# Pwr_Brd_4.net
KiCad netlist of a schematic drawn in Altium Designer
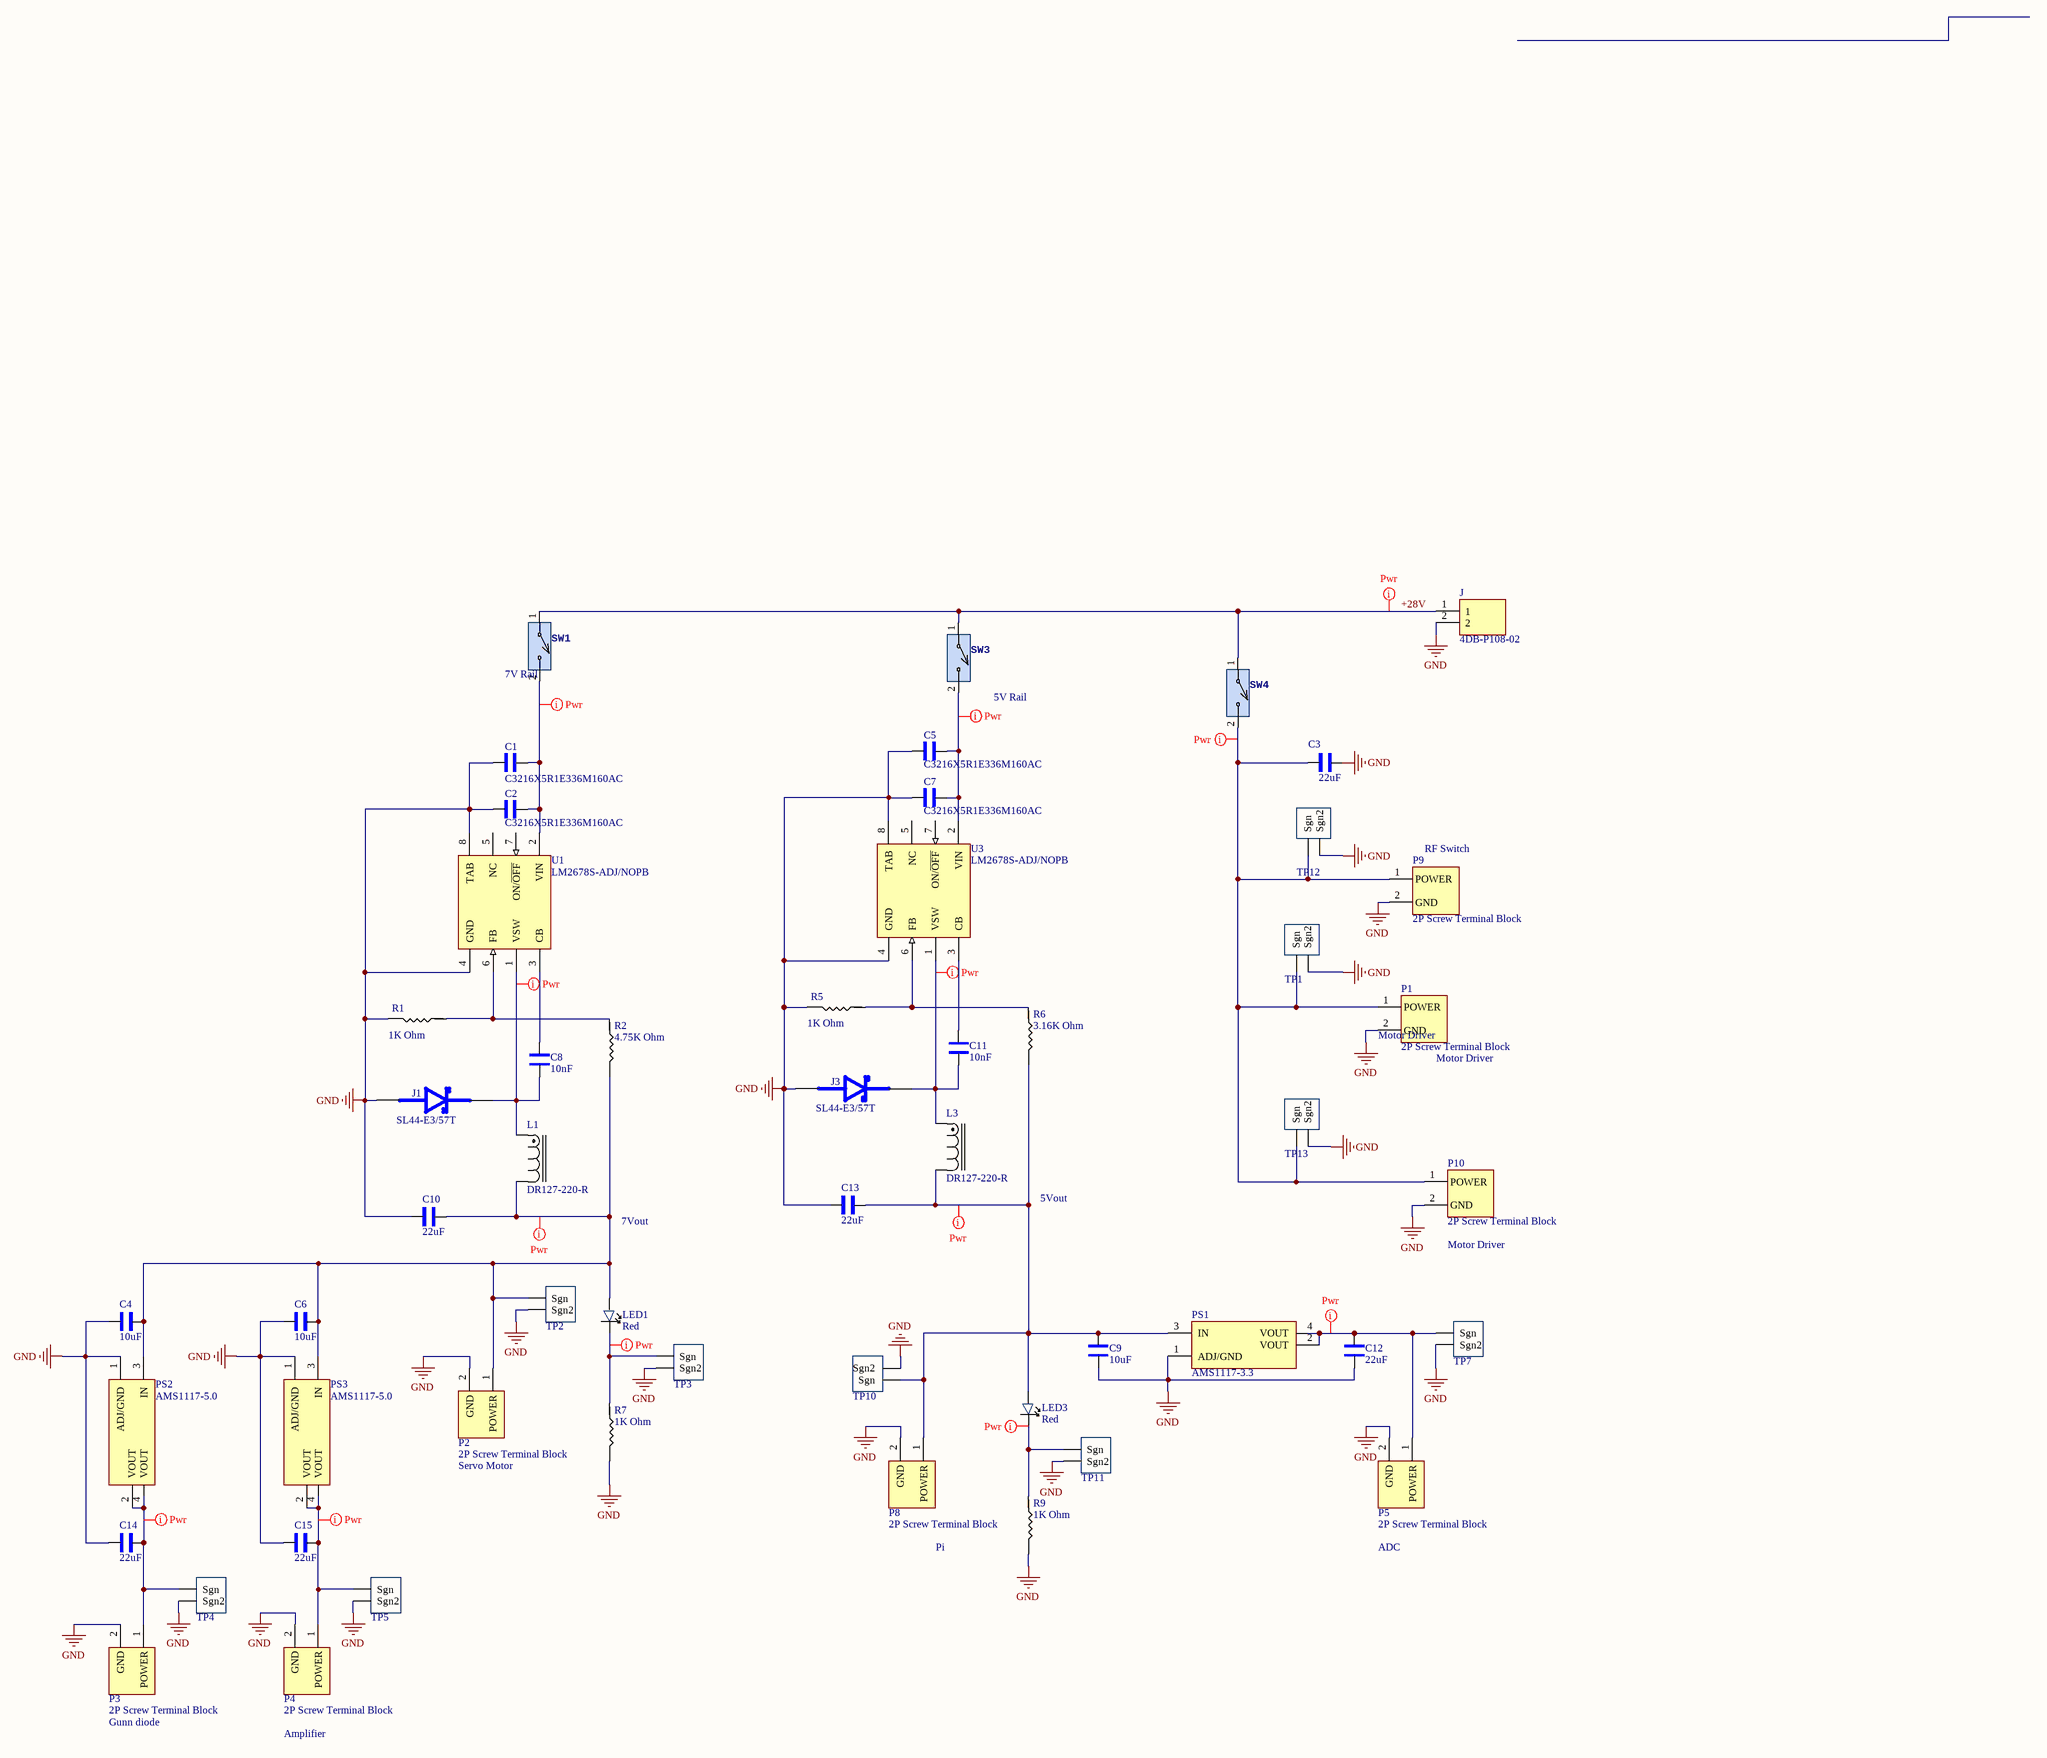
[diagram p0: Pwr_Brd_4.SchDoc]

(export (version "E")
  (design (tool "Eeschema 10.0.6"))
  (components
    (comp (ref "C1")
      (value "C3216X5R1E336M160AC")
      (footprint "CAPC3216X180N")
      (description "Cap Ceramic 33uF 25V X5R 20% Pad SMD 1206 85Â°C Low ESR T/R")
      (fields (field (name "MF") "TDK Electronics"))
      (libsource (lib "C3216X5R1E336M160AC") (part "C3216X5R1E336M160AC"))
    )
    (comp (ref "C2")
      (value "C3216X5R1E336M160AC")
      (footprint "CAPC3216X180N")
      (description "Cap Ceramic 33uF 25V X5R 20% Pad SMD 1206 85Â°C Low ESR T/R")
      (fields (field (name "MF") "TDK Electronics"))
      (libsource (lib "C3216X5R1E336M160AC") (part "C3216X5R1E336M160AC"))
    )
    (comp (ref "C3")
      (value "22uF")
      (footprint "1206_Passive_Capacitor")
      (description "22uF ±10% 25V X5R 1206 Multilayer Ceramic Capacitors MLCC - SMD/SMT RoHS")
      (fields (field (name "MFR PART #") "CL31A226KAHNNNE") (field (name "LCSC PART#") "C12891"))
      (libsource (lib "Capstone_Stock_Library") (part "C_22uF_1206"))
    )
    (comp (ref "C4")
      (value "10uF")
      (footprint "1206_Passive_Capacitor")
      (description "10uF ±10% 50V X5R 1206 Multilayer Ceramic Capacitors MLCC - SMD/SMT RoHS")
      (fields (field (name "LCSC PART#") "C13585") (field (name "MFR PART #") "CL31A106KBHNNNE"))
      (libsource (lib "Capstone_Stock_Library") (part "C_10uF_1206"))
    )
    (comp (ref "C5")
      (value "C3216X5R1E336M160AC")
      (footprint "CAPC3216X180N")
      (description "Cap Ceramic 33uF 25V X5R 20% Pad SMD 1206 85Â°C Low ESR T/R")
      (fields (field (name "MF") "TDK Electronics"))
      (libsource (lib "C3216X5R1E336M160AC") (part "C3216X5R1E336M160AC"))
    )
    (comp (ref "C6")
      (value "10uF")
      (footprint "1206_Passive_Capacitor")
      (description "10uF ±10% 50V X5R 1206 Multilayer Ceramic Capacitors MLCC - SMD/SMT RoHS")
      (fields (field (name "LCSC PART#") "C13585") (field (name "MFR PART #") "CL31A106KBHNNNE"))
      (libsource (lib "Capstone_Stock_Library") (part "C_10uF_1206"))
    )
    (comp (ref "C7")
      (value "C3216X5R1E336M160AC")
      (footprint "CAPC3216X180N")
      (description "Cap Ceramic 33uF 25V X5R 20% Pad SMD 1206 85Â°C Low ESR T/R")
      (fields (field (name "MF") "TDK Electronics"))
      (libsource (lib "C3216X5R1E336M160AC") (part "C3216X5R1E336M160AC"))
    )
    (comp (ref "C8")
      (value "10nF")
      (footprint "1206_Passive_Capacitor")
      (description "10nF 50V X7R ±10% 1206 Multilayer Ceramic Capacitors MLCC - SMD/SMT ROHS")
      (fields (field (name "MFR PART #") "CL31B105KBHNNNE") (field (name "LCSC PART#") "C1848"))
      (libsource (lib "Capstone_Stock_Library") (part "C_10nF_1206"))
    )
    (comp (ref "C9")
      (value "10uF")
      (footprint "1206_Passive_Capacitor")
      (description "10uF ±10% 50V X5R 1206 Multilayer Ceramic Capacitors MLCC - SMD/SMT RoHS")
      (fields (field (name "LCSC PART#") "C13585") (field (name "MFR PART #") "CL31A106KBHNNNE"))
      (libsource (lib "Capstone_Stock_Library") (part "C_10uF_1206"))
    )
    (comp (ref "C10")
      (value "22uF")
      (footprint "1206_Passive_Capacitor")
      (description "22uF ±10% 25V X5R 1206 Multilayer Ceramic Capacitors MLCC - SMD/SMT RoHS")
      (fields (field (name "MFR PART #") "CL31A226KAHNNNE") (field (name "LCSC PART#") "C12891"))
      (libsource (lib "Capstone_Stock_Library") (part "C_22uF_1206"))
    )
    (comp (ref "C11")
      (value "10nF")
      (footprint "1206_Passive_Capacitor")
      (description "10nF 50V X7R ±10% 1206 Multilayer Ceramic Capacitors MLCC - SMD/SMT ROHS")
      (fields (field (name "MFR PART #") "CL31B105KBHNNNE") (field (name "LCSC PART#") "C1848"))
      (libsource (lib "Capstone_Stock_Library") (part "C_10nF_1206"))
    )
    (comp (ref "C12")
      (value "22uF")
      (footprint "1206_Passive_Capacitor")
      (description "22uF ±10% 25V X5R 1206 Multilayer Ceramic Capacitors MLCC - SMD/SMT RoHS")
      (fields (field (name "MFR PART #") "CL31A226KAHNNNE") (field (name "LCSC PART#") "C12891"))
      (libsource (lib "Capstone_Stock_Library") (part "C_22uF_1206"))
    )
    (comp (ref "C13")
      (value "22uF")
      (footprint "1206_Passive_Capacitor")
      (description "22uF ±10% 25V X5R 1206 Multilayer Ceramic Capacitors MLCC - SMD/SMT RoHS")
      (fields (field (name "MFR PART #") "CL31A226KAHNNNE") (field (name "LCSC PART#") "C12891"))
      (libsource (lib "Capstone_Stock_Library") (part "C_22uF_1206"))
    )
    (comp (ref "C14")
      (value "22uF")
      (footprint "1206_Passive_Capacitor")
      (description "22uF ±10% 25V X5R 1206 Multilayer Ceramic Capacitors MLCC - SMD/SMT RoHS")
      (fields (field (name "MFR PART #") "CL31A226KAHNNNE") (field (name "LCSC PART#") "C12891"))
      (libsource (lib "Capstone_Stock_Library") (part "C_22uF_1206"))
    )
    (comp (ref "C15")
      (value "22uF")
      (footprint "1206_Passive_Capacitor")
      (description "22uF ±10% 25V X5R 1206 Multilayer Ceramic Capacitors MLCC - SMD/SMT RoHS")
      (fields (field (name "MFR PART #") "CL31A226KAHNNNE") (field (name "LCSC PART#") "C12891"))
      (libsource (lib "Capstone_Stock_Library") (part "C_22uF_1206"))
    )
    (comp (ref "J")
      (value "4DB-P108-02")
      (footprint "TE_2-1437667-4")
      (description "Conn; Term Strip; Barrier; 2Pole; 8.26mmPitch; SnglRow; 22-12; Series 4DB; 20A; 150V")
      (fields (field (name "MF") "TE Connectivity"))
      (libsource (lib "4DB-P108-02") (part "4DB-P108-02"))
    )
    (comp (ref "J1")
      (value "SL44-E3/57T")
      (footprint "DIOM7959X262N")
      (description "Diode Schottky 40 V 4A Surface Mount DO-214AB (SMC)")
      (fields (field (name "MF") "Vishay Semiconductor"))
      (libsource (lib "SL44-E3_57T") (part "SL44-E3/57T"))
    )
    (comp (ref "J3")
      (value "SL44-E3/57T")
      (footprint "DIOM7959X262N")
      (description "Diode Schottky 40 V 4A Surface Mount DO-214AB (SMC)")
      (fields (field (name "MF") "Vishay Semiconductor"))
      (libsource (lib "SL44-E3_57T") (part "SL44-E3/57T"))
    )
    (comp (ref "L1")
      (value "DR127-220-R")
      (footprint "DR127")
      (description "Description")
      (fields (field (name "COPYRIGHT") "Copyright (C) 2025 Ultra Librarian. All rights reserved."))
      (libsource (lib "DR127-220-R") (part "DR127-220-R"))
    )
    (comp (ref "L3")
      (value "DR127-220-R")
      (footprint "DR127")
      (description "Description")
      (fields (field (name "COPYRIGHT") "Copyright (C) 2025 Ultra Librarian. All rights reserved."))
      (libsource (lib "DR127-220-R") (part "DR127-220-R"))
    )
    (comp (ref "LED1")
      (value "Red")
      (footprint "LED_1206")
      (description "Red 621~631nm 1206 Light Emitting Diodes (LED) RoHS")
      (fields (field (name "MFR PART #") "15-21/R6C-FQ1R1B/2T") (field (name "LCSC PART#") "C93133"))
      (libsource (lib "Capstone_Stock_Library") (part "LED_RED_1206"))
    )
    (comp (ref "LED3")
      (value "Red")
      (footprint "LED_1206")
      (description "Red 621~631nm 1206 Light Emitting Diodes (LED) RoHS")
      (fields (field (name "MFR PART #") "15-21/R6C-FQ1R1B/2T") (field (name "LCSC PART#") "C93133"))
      (libsource (lib "Capstone_Stock_Library") (part "LED_RED_1206"))
    )
    (comp (ref "P1")
      (value "2P Screw Terminal Block")
      (footprint "P_Terminal block 3.5mm-pitch")
      (description "Green Straight pin 3.5mm  pitch; P=3.5mm  Screw terminal ROHS")
      (fields (field (name "MFR PART #") "KF350-3.5-2P") (field (name "MANUFACTURER") "Cixi Kefa Elec"))
      (libsource (lib "") (part "P_Terminal block_1"))
    )
    (comp (ref "P2")
      (value "2P Screw Terminal Block")
      (footprint "P_Terminal block 3.5mm-pitch")
      (description "Green Straight pin 3.5mm  pitch; P=3.5mm  Screw terminal ROHS")
      (fields (field (name "MFR PART #") "KF350-3.5-2P") (field (name "MANUFACTURER") "Cixi Kefa Elec"))
      (libsource (lib "Capstone_Stock_Library") (part "P_Terminal block"))
    )
    (comp (ref "P3")
      (value "2P Screw Terminal Block")
      (footprint "P_Terminal block 3.5mm-pitch")
      (description "Green Straight pin 3.5mm  pitch; P=3.5mm  Screw terminal ROHS")
      (fields (field (name "MFR PART #") "KF350-3.5-2P") (field (name "MANUFACTURER") "Cixi Kefa Elec"))
      (libsource (lib "Capstone_Stock_Library") (part "P_Terminal block"))
    )
    (comp (ref "P4")
      (value "2P Screw Terminal Block")
      (footprint "P_Terminal block 3.5mm-pitch")
      (description "Green Straight pin 3.5mm  pitch; P=3.5mm  Screw terminal ROHS")
      (fields (field (name "MFR PART #") "KF350-3.5-2P") (field (name "MANUFACTURER") "Cixi Kefa Elec"))
      (libsource (lib "Capstone_Stock_Library") (part "P_Terminal block"))
    )
    (comp (ref "P5")
      (value "2P Screw Terminal Block")
      (footprint "P_Terminal block 3.5mm-pitch")
      (description "Green Straight pin 3.5mm  pitch; P=3.5mm  Screw terminal ROHS")
      (fields (field (name "MFR PART #") "KF350-3.5-2P") (field (name "MANUFACTURER") "Cixi Kefa Elec"))
      (libsource (lib "Capstone_Stock_Library") (part "P_Terminal block"))
    )
    (comp (ref "P8")
      (value "2P Screw Terminal Block")
      (footprint "P_Terminal block 3.5mm-pitch")
      (description "Green Straight pin 3.5mm  pitch; P=3.5mm  Screw terminal ROHS")
      (fields (field (name "MFR PART #") "KF350-3.5-2P") (field (name "MANUFACTURER") "Cixi Kefa Elec"))
      (libsource (lib "Capstone_Stock_Library") (part "P_Terminal block"))
    )
    (comp (ref "P9")
      (value "2P Screw Terminal Block")
      (footprint "P_Terminal block 3.5mm-pitch")
      (description "Green Straight pin 3.5mm  pitch; P=3.5mm  Screw terminal ROHS")
      (fields (field (name "MFR PART #") "KF350-3.5-2P") (field (name "MANUFACTURER") "Cixi Kefa Elec"))
      (libsource (lib "") (part "P_Terminal block_1"))
    )
    (comp (ref "P10")
      (value "2P Screw Terminal Block")
      (footprint "P_Terminal block 3.5mm-pitch")
      (description "Green Straight pin 3.5mm  pitch; P=3.5mm  Screw terminal ROHS")
      (fields (field (name "MFR PART #") "KF350-3.5-2P") (field (name "MANUFACTURER") "Cixi Kefa Elec"))
      (libsource (lib "") (part "P_Terminal block_1"))
    )
    (comp (ref "PS1")
      (value "AMS1117-3.3")
      (footprint "LDO")
      (description "LOW DROPOUT REGULATORS(LDO) POSITIVE FIXED 1.3V @ 800MA 15V 3.3V 1A SOT-223 ROHS")
      (fields (field (name "LCSC PART#") "C6186"))
      (libsource (lib "Capstone_Stock_Library") (part "PS_AMS_LDO_3v3"))
    )
    (comp (ref "PS2")
      (value "AMS1117-5.0")
      (footprint "LDO")
      (description "LOW DROPOUT REGULATORS(LDO) POSITIVE FIXED 1.3V @ 1A 15V 5V 1A SOT-223 ROHS")
      (fields (field (name "LCSC PART#") "C6187"))
      (libsource (lib "Capstone_Stock_Library") (part "PS_AMS_LDO_5V"))
    )
    (comp (ref "PS3")
      (value "AMS1117-5.0")
      (footprint "LDO")
      (description "LOW DROPOUT REGULATORS(LDO) POSITIVE FIXED 1.3V @ 1A 15V 5V 1A SOT-223 ROHS")
      (fields (field (name "LCSC PART#") "C6187"))
      (libsource (lib "Capstone_Stock_Library") (part "PS_AMS_LDO_5V"))
    )
    (comp (ref "R1")
      (value "1K Ohm")
      (footprint "1206_Passive_Resitor")
      (description "CHIP RESISTOR - SURFACE MOUNT 1KOHMS ±1% 1/4W 1206 ROHS")
      (fields (field (name "MFR PART #") "RNCP1206FTD1K00CT") (field (name "LCSC PART#") "C4410"))
      (libsource (lib "Capstone_Stock_Library") (part "R_1K_1206"))
    )
    (comp (ref "R2")
      (value "4.75K Ohm")
      (footprint "1206_Passive_Resitor")
      (description "CHIP RESISTOR - SURFACE MOUNT 1KOHMS ±1% 1/4W 1206 ROHS")
      (fields (field (name "MFR PART #") "RNCP1206FTD1K00CT") (field (name "LCSC PART#") "C4410"))
      (libsource (lib "Capstone_Stock_Library") (part "R_1K_1206"))
    )
    (comp (ref "R5")
      (value "1K Ohm")
      (footprint "1206_Passive_Resitor")
      (description "CHIP RESISTOR - SURFACE MOUNT 1KOHMS ±1% 1/4W 1206 ROHS")
      (fields (field (name "MFR PART #") "RNCP1206FTD1K00CT") (field (name "LCSC PART#") "C4410"))
      (libsource (lib "Capstone_Stock_Library") (part "R_1K_1206"))
    )
    (comp (ref "R6")
      (value "3.16K Ohm")
      (footprint "1206_Passive_Resitor")
      (description "CHIP RESISTOR - SURFACE MOUNT 1KOHMS ±1% 1/4W 1206 ROHS")
      (fields (field (name "MFR PART #") "RNCP1206FTD1K00CT") (field (name "LCSC PART#") "C4410"))
      (libsource (lib "Capstone_Stock_Library") (part "R_1K_1206"))
    )
    (comp (ref "R7")
      (value "1K Ohm")
      (footprint "1206_Passive_Resitor")
      (description "CHIP RESISTOR - SURFACE MOUNT 1KOHMS ±1% 1/4W 1206 ROHS")
      (fields (field (name "MFR PART #") "RNCP1206FTD1K00CT") (field (name "LCSC PART#") "C4410"))
      (libsource (lib "Capstone_Stock_Library") (part "R_1K_1206"))
    )
    (comp (ref "R9")
      (value "1K Ohm")
      (footprint "1206_Passive_Resitor")
      (description "CHIP RESISTOR - SURFACE MOUNT 1KOHMS ±1% 1/4W 1206 ROHS")
      (fields (field (name "MFR PART #") "RNCP1206FTD1K00CT") (field (name "LCSC PART#") "C4410"))
      (libsource (lib "Capstone_Stock_Library") (part "R_1K_1206"))
    )
    (comp (ref "SW1")
      (value "SW_2Pin_100mil_Switch")
      (footprint "2Pin-Header-Conn")
      (description "2Pin Header")
      (fields (field (name "LCSC PART#") "C124375"))
      (libsource (lib "Capstone_Stock_Library") (part "SW_2Pin_100mil_Switch"))
    )
    (comp (ref "SW3")
      (value "SW_2Pin_100mil_Switch")
      (footprint "2Pin-Header-Conn")
      (description "2Pin Header")
      (fields (field (name "LCSC PART#") "C124375"))
      (libsource (lib "Capstone_Stock_Library") (part "SW_2Pin_100mil_Switch"))
    )
    (comp (ref "SW4")
      (value "SW_2Pin_100mil_Switch")
      (footprint "2Pin-Header-Conn")
      (description "2Pin Header")
      (fields (field (name "LCSC PART#") "C124375"))
      (libsource (lib "Capstone_Stock_Library") (part "SW_2Pin_100mil_Switch"))
    )
    (comp (ref "TP1")
      (value "10x Probe TP")
      (footprint "TP_Diff_Probe")
      (description "Test Point 300 mil centers")
      (libsource (lib "Capstone_Stock_Library") (part "TP_Diff_Probe"))
    )
    (comp (ref "TP2")
      (value "10x Probe TP")
      (footprint "TP_Diff_Probe")
      (description "Test Point 300 mil centers")
      (libsource (lib "") (part "TP_Diff_Probe_1"))
    )
    (comp (ref "TP3")
      (value "10x Probe TP")
      (footprint "TP_Diff_Probe")
      (description "Test Point 300 mil centers")
      (libsource (lib "") (part "TP_Diff_Probe_1"))
    )
    (comp (ref "TP4")
      (value "10x Probe TP")
      (footprint "TP_Diff_Probe")
      (description "Test Point 300 mil centers")
      (libsource (lib "") (part "TP_Diff_Probe_1"))
    )
    (comp (ref "TP5")
      (value "10x Probe TP")
      (footprint "TP_Diff_Probe")
      (description "Test Point 300 mil centers")
      (libsource (lib "") (part "TP_Diff_Probe_1"))
    )
    (comp (ref "TP7")
      (value "10x Probe TP")
      (footprint "TP_Diff_Probe")
      (description "Test Point 300 mil centers")
      (libsource (lib "") (part "TP_Diff_Probe_1"))
    )
    (comp (ref "TP10")
      (value "10x Probe TP")
      (footprint "TP_Diff_Probe")
      (description "Test Point 300 mil centers")
      (libsource (lib "") (part "TP_Diff_Probe_2"))
    )
    (comp (ref "TP11")
      (value "10x Probe TP")
      (footprint "TP_Diff_Probe")
      (description "Test Point 300 mil centers")
      (libsource (lib "") (part "TP_Diff_Probe_1"))
    )
    (comp (ref "TP12")
      (value "10x Probe TP")
      (footprint "TP_Diff_Probe")
      (description "Test Point 300 mil centers")
      (libsource (lib "Capstone_Stock_Library") (part "TP_Diff_Probe"))
    )
    (comp (ref "TP13")
      (value "10x Probe TP")
      (footprint "TP_Diff_Probe")
      (description "Test Point 300 mil centers")
      (libsource (lib "Capstone_Stock_Library") (part "TP_Diff_Probe"))
    )
    (comp (ref "U1")
      (value "LM2678S-ADJ/NOPB")
      (footprint "KTW0007B_N")
      (description "SIMPLE SWITCHER® High Efficiency 5A Step-Down Voltage Regulator, 7-pin TO-263, Pb-Free")
      (fields (field (name "MANUFACTURER") "Texas Instruments"))
      (libsource (lib "Altium Content Vault") (part "PM-REG-LM2678S"))
    )
    (comp (ref "U3")
      (value "LM2678S-ADJ/NOPB")
      (footprint "KTW0007B_N")
      (description "SIMPLE SWITCHER® High Efficiency 5A Step-Down Voltage Regulator, 7-pin TO-263, Pb-Free")
      (fields (field (name "MANUFACTURER") "Texas Instruments"))
      (libsource (lib "Altium Content Vault") (part "PM-REG-LM2678S"))
    )
  )
  (nets
    (net (code "1") (name "/+28V") (class "Default")
      (node (ref "J") (pin "1") (pinfunction "1_1") (pintype "passive"))
      (node (ref "SW1") (pin "1") (pinfunction "1_1") (pintype "passive"))
      (node (ref "SW3") (pin "1") (pinfunction "1_1") (pintype "passive"))
      (node (ref "SW4") (pin "1") (pinfunction "1_1") (pintype "passive"))
    )
    (net (code "2") (name "GND") (class "Default")
      (node (ref "C1") (pin "1") (pinfunction "1_1") (pintype "passive"))
      (node (ref "C10") (pin "1") (pinfunction "1_1") (pintype "passive"))
      (node (ref "C12") (pin "1") (pinfunction "1_1") (pintype "passive"))
      (node (ref "C13") (pin "1") (pinfunction "1_1") (pintype "passive"))
      (node (ref "C14") (pin "1") (pinfunction "1_1") (pintype "passive"))
      (node (ref "C15") (pin "1") (pinfunction "1_1") (pintype "passive"))
      (node (ref "C2") (pin "1") (pinfunction "1_1") (pintype "passive"))
      (node (ref "C3") (pin "2") (pinfunction "2_2") (pintype "passive"))
      (node (ref "C4") (pin "1") (pinfunction "1_1") (pintype "passive"))
      (node (ref "C5") (pin "1") (pinfunction "1_1") (pintype "passive"))
      (node (ref "C6") (pin "1") (pinfunction "1_1") (pintype "passive"))
      (node (ref "C7") (pin "1") (pinfunction "1_1") (pintype "passive"))
      (node (ref "C9") (pin "1") (pinfunction "1_1") (pintype "passive"))
      (node (ref "J") (pin "2") (pinfunction "2_2") (pintype "passive"))
      (node (ref "J1") (pin "A") (pinfunction "A_A") (pintype "passive"))
      (node (ref "J3") (pin "A") (pinfunction "A_A") (pintype "passive"))
      (node (ref "P1") (pin "2") (pinfunction "GND_2") (pintype "passive"))
      (node (ref "P10") (pin "2") (pinfunction "GND_2") (pintype "passive"))
      (node (ref "P2") (pin "2") (pinfunction "GND_2") (pintype "passive"))
      (node (ref "P3") (pin "2") (pinfunction "GND_2") (pintype "passive"))
      (node (ref "P4") (pin "2") (pinfunction "GND_2") (pintype "passive"))
      (node (ref "P5") (pin "2") (pinfunction "GND_2") (pintype "passive"))
      (node (ref "P8") (pin "2") (pinfunction "GND_2") (pintype "passive"))
      (node (ref "P9") (pin "2") (pinfunction "GND_2") (pintype "passive"))
      (node (ref "PS1") (pin "1") (pinfunction "ADJ/GND_1") (pintype "passive"))
      (node (ref "PS2") (pin "1") (pinfunction "ADJ/GND_1") (pintype "passive"))
      (node (ref "PS3") (pin "1") (pinfunction "ADJ/GND_1") (pintype "passive"))
      (node (ref "R1") (pin "2") (pinfunction "2_2") (pintype "passive"))
      (node (ref "R5") (pin "2") (pinfunction "2_2") (pintype "passive"))
      (node (ref "R7") (pin "2") (pinfunction "2_2") (pintype "passive"))
      (node (ref "R9") (pin "2") (pinfunction "2_2") (pintype "passive"))
      (node (ref "TP1") (pin "2") (pinfunction "Sgn2_2") (pintype "passive"))
      (node (ref "TP10") (pin "2") (pinfunction "Sgn2_2") (pintype "passive"))
      (node (ref "TP11") (pin "2") (pinfunction "Sgn2_2") (pintype "passive"))
      (node (ref "TP12") (pin "2") (pinfunction "Sgn2_2") (pintype "passive"))
      (node (ref "TP13") (pin "2") (pinfunction "Sgn2_2") (pintype "passive"))
      (node (ref "TP2") (pin "2") (pinfunction "Sgn2_2") (pintype "passive"))
      (node (ref "TP3") (pin "2") (pinfunction "Sgn2_2") (pintype "passive"))
      (node (ref "TP4") (pin "2") (pinfunction "Sgn2_2") (pintype "passive"))
      (node (ref "TP5") (pin "2") (pinfunction "Sgn2_2") (pintype "passive"))
      (node (ref "TP7") (pin "2") (pinfunction "Sgn2_2") (pintype "passive"))
      (node (ref "U1") (pin "4") (pinfunction "GND_4") (pintype "power_in"))
      (node (ref "U1") (pin "8") (pinfunction "TAB_8") (pintype "power_in"))
      (node (ref "U3") (pin "4") (pinfunction "GND_4") (pintype "power_in"))
      (node (ref "U3") (pin "8") (pinfunction "TAB_8") (pintype "power_in"))
    )
    (net (code "3") (name "Net-(P1-POWER)") (class "Default")
      (node (ref "C3") (pin "1") (pinfunction "1_1") (pintype "passive"))
      (node (ref "P1") (pin "1") (pinfunction "POWER_1") (pintype "passive"))
      (node (ref "P10") (pin "1") (pinfunction "POWER_1") (pintype "passive"))
      (node (ref "P9") (pin "1") (pinfunction "POWER_1") (pintype "passive"))
      (node (ref "SW4") (pin "2") (pinfunction "2_2") (pintype "passive"))
      (node (ref "TP1") (pin "1") (pinfunction "Sgn_1") (pintype "passive"))
      (node (ref "TP12") (pin "1") (pinfunction "Sgn_1") (pintype "passive"))
      (node (ref "TP13") (pin "1") (pinfunction "Sgn_1") (pintype "passive"))
    )
    (net (code "4") (name "Net-(P2-POWER)") (class "Default")
      (node (ref "C10") (pin "2") (pinfunction "2_2") (pintype "passive"))
      (node (ref "C4") (pin "2") (pinfunction "2_2") (pintype "passive"))
      (node (ref "C6") (pin "2") (pinfunction "2_2") (pintype "passive"))
      (node (ref "L1") (pin "2") (pinfunction "2_2") (pintype "passive"))
      (node (ref "LED1") (pin "1") (pinfunction "1_1") (pintype "passive"))
      (node (ref "P2") (pin "1") (pinfunction "POWER_1") (pintype "passive"))
      (node (ref "PS2") (pin "3") (pinfunction "IN_3") (pintype "power_in"))
      (node (ref "PS3") (pin "3") (pinfunction "IN_3") (pintype "power_in"))
      (node (ref "R2") (pin "2") (pinfunction "2_2") (pintype "passive"))
      (node (ref "TP2") (pin "1") (pinfunction "Sgn_1") (pintype "passive"))
    )
    (net (code "5") (name "Net-(P3-POWER)") (class "Default")
      (node (ref "C14") (pin "2") (pinfunction "2_2") (pintype "passive"))
      (node (ref "P3") (pin "1") (pinfunction "POWER_1") (pintype "passive"))
      (node (ref "PS2") (pin "2") (pinfunction "VOUT_2") (pintype "power_in"))
      (node (ref "PS2") (pin "4") (pinfunction "VOUT_4") (pintype "power_in"))
      (node (ref "TP4") (pin "1") (pinfunction "Sgn_1") (pintype "passive"))
    )
    (net (code "6") (name "Net-(P4-POWER)") (class "Default")
      (node (ref "C15") (pin "2") (pinfunction "2_2") (pintype "passive"))
      (node (ref "P4") (pin "1") (pinfunction "POWER_1") (pintype "passive"))
      (node (ref "PS3") (pin "2") (pinfunction "VOUT_2") (pintype "power_in"))
      (node (ref "PS3") (pin "4") (pinfunction "VOUT_4") (pintype "power_in"))
      (node (ref "TP5") (pin "1") (pinfunction "Sgn_1") (pintype "passive"))
    )
    (net (code "7") (name "Net-(P5-POWER)") (class "Default")
      (node (ref "C12") (pin "2") (pinfunction "2_2") (pintype "passive"))
      (node (ref "P5") (pin "1") (pinfunction "POWER_1") (pintype "passive"))
      (node (ref "PS1") (pin "2") (pinfunction "VOUT_2") (pintype "power_in"))
      (node (ref "PS1") (pin "4") (pinfunction "VOUT_4") (pintype "power_in"))
      (node (ref "TP7") (pin "1") (pinfunction "Sgn_1") (pintype "passive"))
    )
    (net (code "8") (name "Net-(P8-POWER)") (class "Default")
      (node (ref "C13") (pin "2") (pinfunction "2_2") (pintype "passive"))
      (node (ref "C9") (pin "2") (pinfunction "2_2") (pintype "passive"))
      (node (ref "L3") (pin "2") (pinfunction "2_2") (pintype "passive"))
      (node (ref "LED3") (pin "1") (pinfunction "1_1") (pintype "passive"))
      (node (ref "P8") (pin "1") (pinfunction "POWER_1") (pintype "passive"))
      (node (ref "PS1") (pin "3") (pinfunction "IN_3") (pintype "power_in"))
      (node (ref "R6") (pin "2") (pinfunction "2_2") (pintype "passive"))
      (node (ref "TP10") (pin "1") (pinfunction "Sgn_1") (pintype "passive"))
    )
    (net (code "9") (name "Net-(TP3-Sgn)") (class "Default")
      (node (ref "LED1") (pin "2") (pinfunction "2_2") (pintype "passive"))
      (node (ref "R7") (pin "1") (pinfunction "1_1") (pintype "passive"))
      (node (ref "TP3") (pin "1") (pinfunction "Sgn_1") (pintype "passive"))
    )
    (net (code "10") (name "Net-(TP11-Sgn)") (class "Default")
      (node (ref "LED3") (pin "2") (pinfunction "2_2") (pintype "passive"))
      (node (ref "R9") (pin "1") (pinfunction "1_1") (pintype "passive"))
      (node (ref "TP11") (pin "1") (pinfunction "Sgn_1") (pintype "passive"))
    )
    (net (code "11") (name "Net-(U1-CB)") (class "Default")
      (node (ref "C8") (pin "2") (pinfunction "2_2") (pintype "passive"))
      (node (ref "U1") (pin "3") (pinfunction "CB_3") (pintype "passive"))
    )
    (net (code "12") (name "Net-(U1-FB)") (class "Default")
      (node (ref "R1") (pin "1") (pinfunction "1_1") (pintype "passive"))
      (node (ref "R2") (pin "1") (pinfunction "1_1") (pintype "passive"))
      (node (ref "U1") (pin "6") (pinfunction "FB_6") (pintype "input"))
    )
    (net (code "13") (name "Net-(U1-VIN)") (class "Default")
      (node (ref "C1") (pin "2") (pinfunction "2_2") (pintype "passive"))
      (node (ref "C2") (pin "2") (pinfunction "2_2") (pintype "passive"))
      (node (ref "SW1") (pin "2") (pinfunction "2_2") (pintype "passive"))
      (node (ref "U1") (pin "2") (pinfunction "VIN_2") (pintype "power_in"))
    )
    (net (code "14") (name "Net-(U1-VSW)") (class "Default")
      (node (ref "C8") (pin "1") (pinfunction "1_1") (pintype "passive"))
      (node (ref "J1") (pin "C") (pinfunction "C_C") (pintype "passive"))
      (node (ref "L1") (pin "1") (pinfunction "1_1") (pintype "passive"))
      (node (ref "U1") (pin "1") (pinfunction "VSW_1") (pintype "power_in"))
    )
    (net (code "15") (name "Net-(U3-CB)") (class "Default")
      (node (ref "C11") (pin "2") (pinfunction "2_2") (pintype "passive"))
      (node (ref "U3") (pin "3") (pinfunction "CB_3") (pintype "passive"))
    )
    (net (code "16") (name "Net-(U3-FB)") (class "Default")
      (node (ref "R5") (pin "1") (pinfunction "1_1") (pintype "passive"))
      (node (ref "R6") (pin "1") (pinfunction "1_1") (pintype "passive"))
      (node (ref "U3") (pin "6") (pinfunction "FB_6") (pintype "input"))
    )
    (net (code "17") (name "Net-(U3-VIN)") (class "Default")
      (node (ref "C5") (pin "2") (pinfunction "2_2") (pintype "passive"))
      (node (ref "C7") (pin "2") (pinfunction "2_2") (pintype "passive"))
      (node (ref "SW3") (pin "2") (pinfunction "2_2") (pintype "passive"))
      (node (ref "U3") (pin "2") (pinfunction "VIN_2") (pintype "power_in"))
    )
    (net (code "18") (name "Net-(U3-VSW)") (class "Default")
      (node (ref "C11") (pin "1") (pinfunction "1_1") (pintype "passive"))
      (node (ref "J3") (pin "C") (pinfunction "C_C") (pintype "passive"))
      (node (ref "L3") (pin "1") (pinfunction "1_1") (pintype "passive"))
      (node (ref "U3") (pin "1") (pinfunction "VSW_1") (pintype "power_in"))
    )
    (net (code "19") (name "unconnected-(U1-NC-Pad5)") (class "Default")
      (node (ref "U1") (pin "5") (pinfunction "NC_5") (pintype "passive"))
    )
    (net (code "20") (name "unconnected-(U1-ON{slash}~{OFF}-Pad7)") (class "Default")
      (node (ref "U1") (pin "7") (pinfunction "ON/~{OFF}_7") (pintype "input"))
    )
    (net (code "21") (name "unconnected-(U3-NC-Pad5)") (class "Default")
      (node (ref "U3") (pin "5") (pinfunction "NC_5") (pintype "passive"))
    )
    (net (code "22") (name "unconnected-(U3-ON{slash}~{OFF}-Pad7)") (class "Default")
      (node (ref "U3") (pin "7") (pinfunction "ON/~{OFF}_7") (pintype "input"))
    )
  )
)
